# BW1092_IMX378.net
KiCad netlist of a schematic drawn in Altium Designer
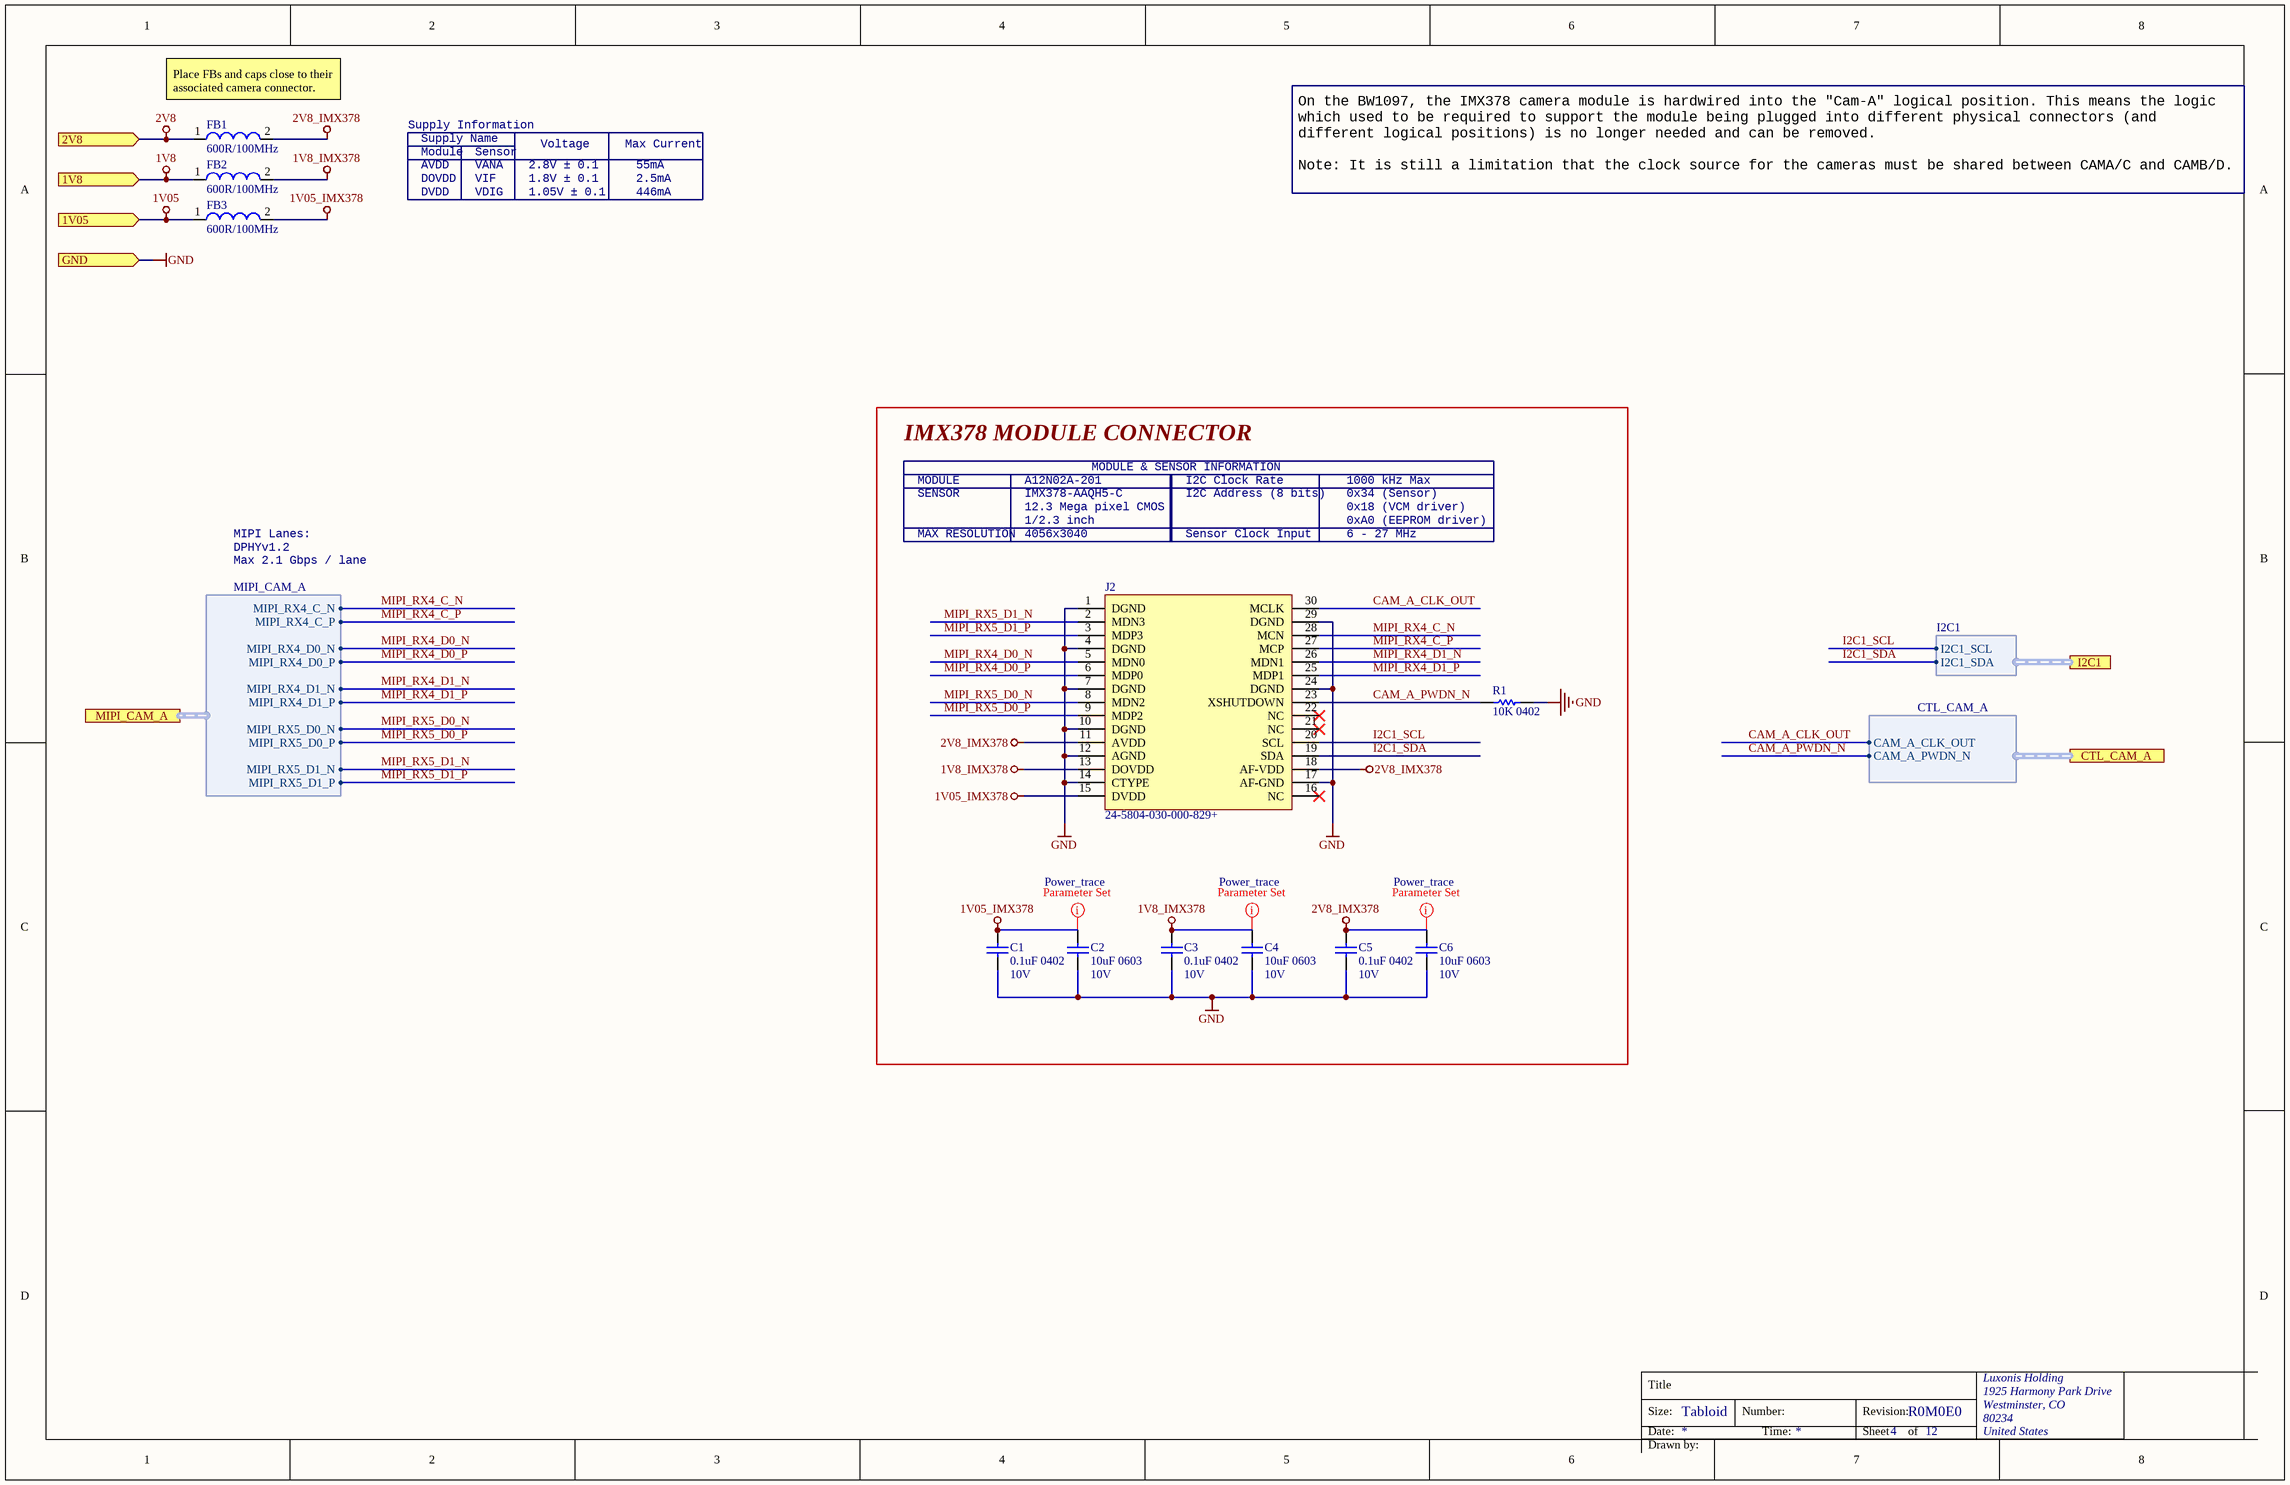
[diagram p0: BW1092_IMX378.SchDoc]

(export (version "E")
  (design (tool "Eeschema 10.0.6"))
  (components
    (comp (ref "C1")
      (value "0.1uF 0402")
      (footprint "CAP_Altium_Vault_Generic:CAPC0402(1005)70_L")
      (description "CAP CER 0.1UF 10V X7R 0402 5%")
      (fields (field (name "TOLERANCE") "5%") (field (name "VOLTAGE RATING") "10V"))
      (libsource (lib "LuxonisMaster") (part "GRM155R71A104JA01D"))
    )
    (comp (ref "C2")
      (value "10uF 0603")
      (footprint "CAP_Altium_Vault_Generic:CAPC0603(1608)100_L")
      (description "CAP CER 10UF 10V X5R 0603 20%")
      (fields (field (name "TOLERANCE") "20%") (field (name "VOLTAGE RATING") "10V"))
      (libsource (lib "LuxonisMaster") (part "GRM188R61A106ME69D"))
    )
    (comp (ref "C3")
      (value "0.1uF 0402")
      (footprint "CAP_Altium_Vault_Generic:CAPC0402(1005)70_L")
      (description "CAP CER 0.1UF 10V X7R 0402 5%")
      (fields (field (name "TOLERANCE") "5%") (field (name "VOLTAGE RATING") "10V"))
      (libsource (lib "LuxonisMaster") (part "GRM155R71A104JA01D"))
    )
    (comp (ref "C4")
      (value "10uF 0603")
      (footprint "CAP_Altium_Vault_Generic:CAPC0603(1608)100_L")
      (description "CAP CER 10UF 10V X5R 0603 20%")
      (fields (field (name "TOLERANCE") "20%") (field (name "VOLTAGE RATING") "10V"))
      (libsource (lib "LuxonisMaster") (part "GRM188R61A106ME69D"))
    )
    (comp (ref "C5")
      (value "0.1uF 0402")
      (footprint "CAP_Altium_Vault_Generic:CAPC0402(1005)70_L")
      (description "CAP CER 0.1UF 10V X7R 0402 5%")
      (fields (field (name "TOLERANCE") "5%") (field (name "VOLTAGE RATING") "10V"))
      (libsource (lib "LuxonisMaster") (part "GRM155R71A104JA01D"))
    )
    (comp (ref "C6")
      (value "10uF 0603")
      (footprint "CAP_Altium_Vault_Generic:CAPC0603(1608)100_L")
      (description "CAP CER 10UF 10V X5R 0603 20%")
      (fields (field (name "TOLERANCE") "20%") (field (name "VOLTAGE RATING") "10V"))
      (libsource (lib "LuxonisMaster") (part "GRM188R61A106ME69D"))
    )
    (comp (ref "FB1")
      (value "600R/100MHz")
      (footprint "LuxonisMaster:2508056017Y2")
      (description "FERRITE BEAD, 0.1OHM, 2A, 0805, 600R/100MHz")
      (fields (field (name "TOLERANCE") "25%"))
      (libsource (lib "LuxonisMaster") (part "2508056017Y2"))
    )
    (comp (ref "FB2")
      (value "600R/100MHz")
      (footprint "LuxonisMaster:2508056017Y2")
      (description "FERRITE BEAD, 0.1OHM, 2A, 0805, 600R/100MHz")
      (fields (field (name "TOLERANCE") "25%"))
      (libsource (lib "LuxonisMaster") (part "2508056017Y2"))
    )
    (comp (ref "FB3")
      (value "600R/100MHz")
      (footprint "LuxonisMaster:2508056017Y2")
      (description "FERRITE BEAD, 0.1OHM, 2A, 0805, 600R/100MHz")
      (fields (field (name "TOLERANCE") "25%"))
      (libsource (lib "LuxonisMaster") (part "2508056017Y2"))
    )
    (comp (ref "J2")
      (value "24-5804-030-000-829+")
      (footprint "LuxonisMaster:A12N02A-201_MatedModule")
      (description "CONN Series 5804 board to board 0.4mm pitch 30 way connector")
      (libsource (lib "LuxonisMaster") (part "A12N02A-201_Connector"))
    )
    (comp (ref "R1")
      (value "10K 0402")
      (footprint "RES_Altium_Vault_Generic:RESC0402(1005)_L")
      (fields (field (name "TOLERANCE") "1%"))
      (libsource (lib "LuxonisMaster") (part "RC0402FR-1310KL"))
    )
  )
  (nets
    (net (code "4") (name "/CAM_A_CLK_OUT") (class "Default")
      (node (ref "J2") (pin "30") (pinfunction "MCLK_30") (pintype "passive"))
    )
    (net (code "5") (name "/CAM_A_PWDN_N") (class "Default")
      (node (ref "J2") (pin "23") (pinfunction "XSHUTDOWN_23") (pintype "passive"))
      (node (ref "R1") (pin "1") (pinfunction "1_1") (pintype "passive"))
    )
    (net (code "6") (name "/I2C1_SCL") (class "Default")
      (node (ref "J2") (pin "20") (pinfunction "SCL_20") (pintype "passive"))
    )
    (net (code "7") (name "/I2C1_SDA") (class "Default")
      (node (ref "J2") (pin "19") (pinfunction "SDA_19") (pintype "passive"))
    )
    (net (code "8") (name "/MIPI_RX4_C_N") (class "Default")
      (node (ref "J2") (pin "28") (pinfunction "MCN_28") (pintype "passive"))
    )
    (net (code "9") (name "/MIPI_RX4_C_P") (class "Default")
      (node (ref "J2") (pin "27") (pinfunction "MCP_27") (pintype "passive"))
    )
    (net (code "10") (name "/MIPI_RX4_D0_N") (class "Default")
      (node (ref "J2") (pin "5") (pinfunction "MDN0_5") (pintype "passive"))
    )
    (net (code "11") (name "/MIPI_RX4_D0_P") (class "Default")
      (node (ref "J2") (pin "6") (pinfunction "MDP0_6") (pintype "passive"))
    )
    (net (code "12") (name "/MIPI_RX4_D1_N") (class "Default")
      (node (ref "J2") (pin "26") (pinfunction "MDN1_26") (pintype "passive"))
    )
    (net (code "13") (name "/MIPI_RX4_D1_P") (class "Default")
      (node (ref "J2") (pin "25") (pinfunction "MDP1_25") (pintype "passive"))
    )
    (net (code "14") (name "/MIPI_RX5_D0_N") (class "Default")
      (node (ref "J2") (pin "8") (pinfunction "MDN2_8") (pintype "passive"))
    )
    (net (code "15") (name "/MIPI_RX5_D0_P") (class "Default")
      (node (ref "J2") (pin "9") (pinfunction "MDP2_9") (pintype "passive"))
    )
    (net (code "16") (name "/MIPI_RX5_D1_N") (class "Default")
      (node (ref "J2") (pin "2") (pinfunction "MDN3_2") (pintype "passive"))
    )
    (net (code "17") (name "/MIPI_RX5_D1_P") (class "Default")
      (node (ref "J2") (pin "3") (pinfunction "MDP3_3") (pintype "passive"))
    )
    (net (code "21") (name "1V05") (class "Default")
      (node (ref "FB3") (pin "1") (pinfunction "1_1") (pintype "passive"))
    )
    (net (code "22") (name "1V05_IMX378") (class "Default")
      (node (ref "C1") (pin "2") (pinfunction "2_2") (pintype "passive"))
      (node (ref "C2") (pin "2") (pinfunction "2_2") (pintype "passive"))
      (node (ref "FB3") (pin "2") (pinfunction "2_2") (pintype "passive"))
      (node (ref "J2") (pin "15") (pinfunction "DVDD_15") (pintype "passive"))
    )
    (net (code "23") (name "1V8") (class "Default")
      (node (ref "FB2") (pin "1") (pinfunction "1_1") (pintype "passive"))
    )
    (net (code "24") (name "1V8_IMX378") (class "Default")
      (node (ref "C3") (pin "2") (pinfunction "2_2") (pintype "passive"))
      (node (ref "C4") (pin "2") (pinfunction "2_2") (pintype "passive"))
      (node (ref "FB2") (pin "2") (pinfunction "2_2") (pintype "passive"))
      (node (ref "J2") (pin "13") (pinfunction "DOVDD_13") (pintype "passive"))
    )
    (net (code "25") (name "2V8") (class "Default")
      (node (ref "FB1") (pin "1") (pinfunction "1_1") (pintype "passive"))
    )
    (net (code "26") (name "2V8_IMX378") (class "Default")
      (node (ref "C5") (pin "2") (pinfunction "2_2") (pintype "passive"))
      (node (ref "C6") (pin "2") (pinfunction "2_2") (pintype "passive"))
      (node (ref "FB1") (pin "2") (pinfunction "2_2") (pintype "passive"))
      (node (ref "J2") (pin "11") (pinfunction "AVDD_11") (pintype "passive"))
      (node (ref "J2") (pin "18") (pinfunction "AF-VDD_18") (pintype "passive"))
    )
    (net (code "27") (name "GND") (class "Default")
      (node (ref "C1") (pin "1") (pinfunction "1_1") (pintype "passive"))
      (node (ref "C2") (pin "1") (pinfunction "1_1") (pintype "passive"))
      (node (ref "C3") (pin "1") (pinfunction "1_1") (pintype "passive"))
      (node (ref "C4") (pin "1") (pinfunction "1_1") (pintype "passive"))
      (node (ref "C5") (pin "1") (pinfunction "1_1") (pintype "passive"))
      (node (ref "C6") (pin "1") (pinfunction "1_1") (pintype "passive"))
      (node (ref "J2") (pin "1") (pinfunction "DGND_1") (pintype "passive"))
      (node (ref "J2") (pin "10") (pinfunction "DGND_10") (pintype "passive"))
      (node (ref "J2") (pin "12") (pinfunction "AGND_12") (pintype "passive"))
      (node (ref "J2") (pin "14") (pinfunction "CTYPE_14") (pintype "passive"))
      (node (ref "J2") (pin "17") (pinfunction "AF-GND_17") (pintype "passive"))
      (node (ref "J2") (pin "24") (pinfunction "DGND_24") (pintype "passive"))
      (node (ref "J2") (pin "29") (pinfunction "DGND_29") (pintype "passive"))
      (node (ref "J2") (pin "4") (pinfunction "DGND_4") (pintype "passive"))
      (node (ref "J2") (pin "7") (pinfunction "DGND_7") (pintype "passive"))
      (node (ref "R1") (pin "2") (pinfunction "2_2") (pintype "passive"))
    )
    (net (code "28") (name "unconnected-(J2-NC-Pad16)") (class "Default")
      (node (ref "J2") (pin "16") (pinfunction "NC_16") (pintype "passive+no_connect"))
    )
    (net (code "29") (name "unconnected-(J2-NC-Pad21)") (class "Default")
      (node (ref "J2") (pin "21") (pinfunction "NC_21") (pintype "passive+no_connect"))
    )
    (net (code "30") (name "unconnected-(J2-NC-Pad22)") (class "Default")
      (node (ref "J2") (pin "22") (pinfunction "NC_22") (pintype "passive+no_connect"))
    )
  )
)
